# WheelDir_BoB.net
KiCad netlist of a schematic drawn in EAGLE
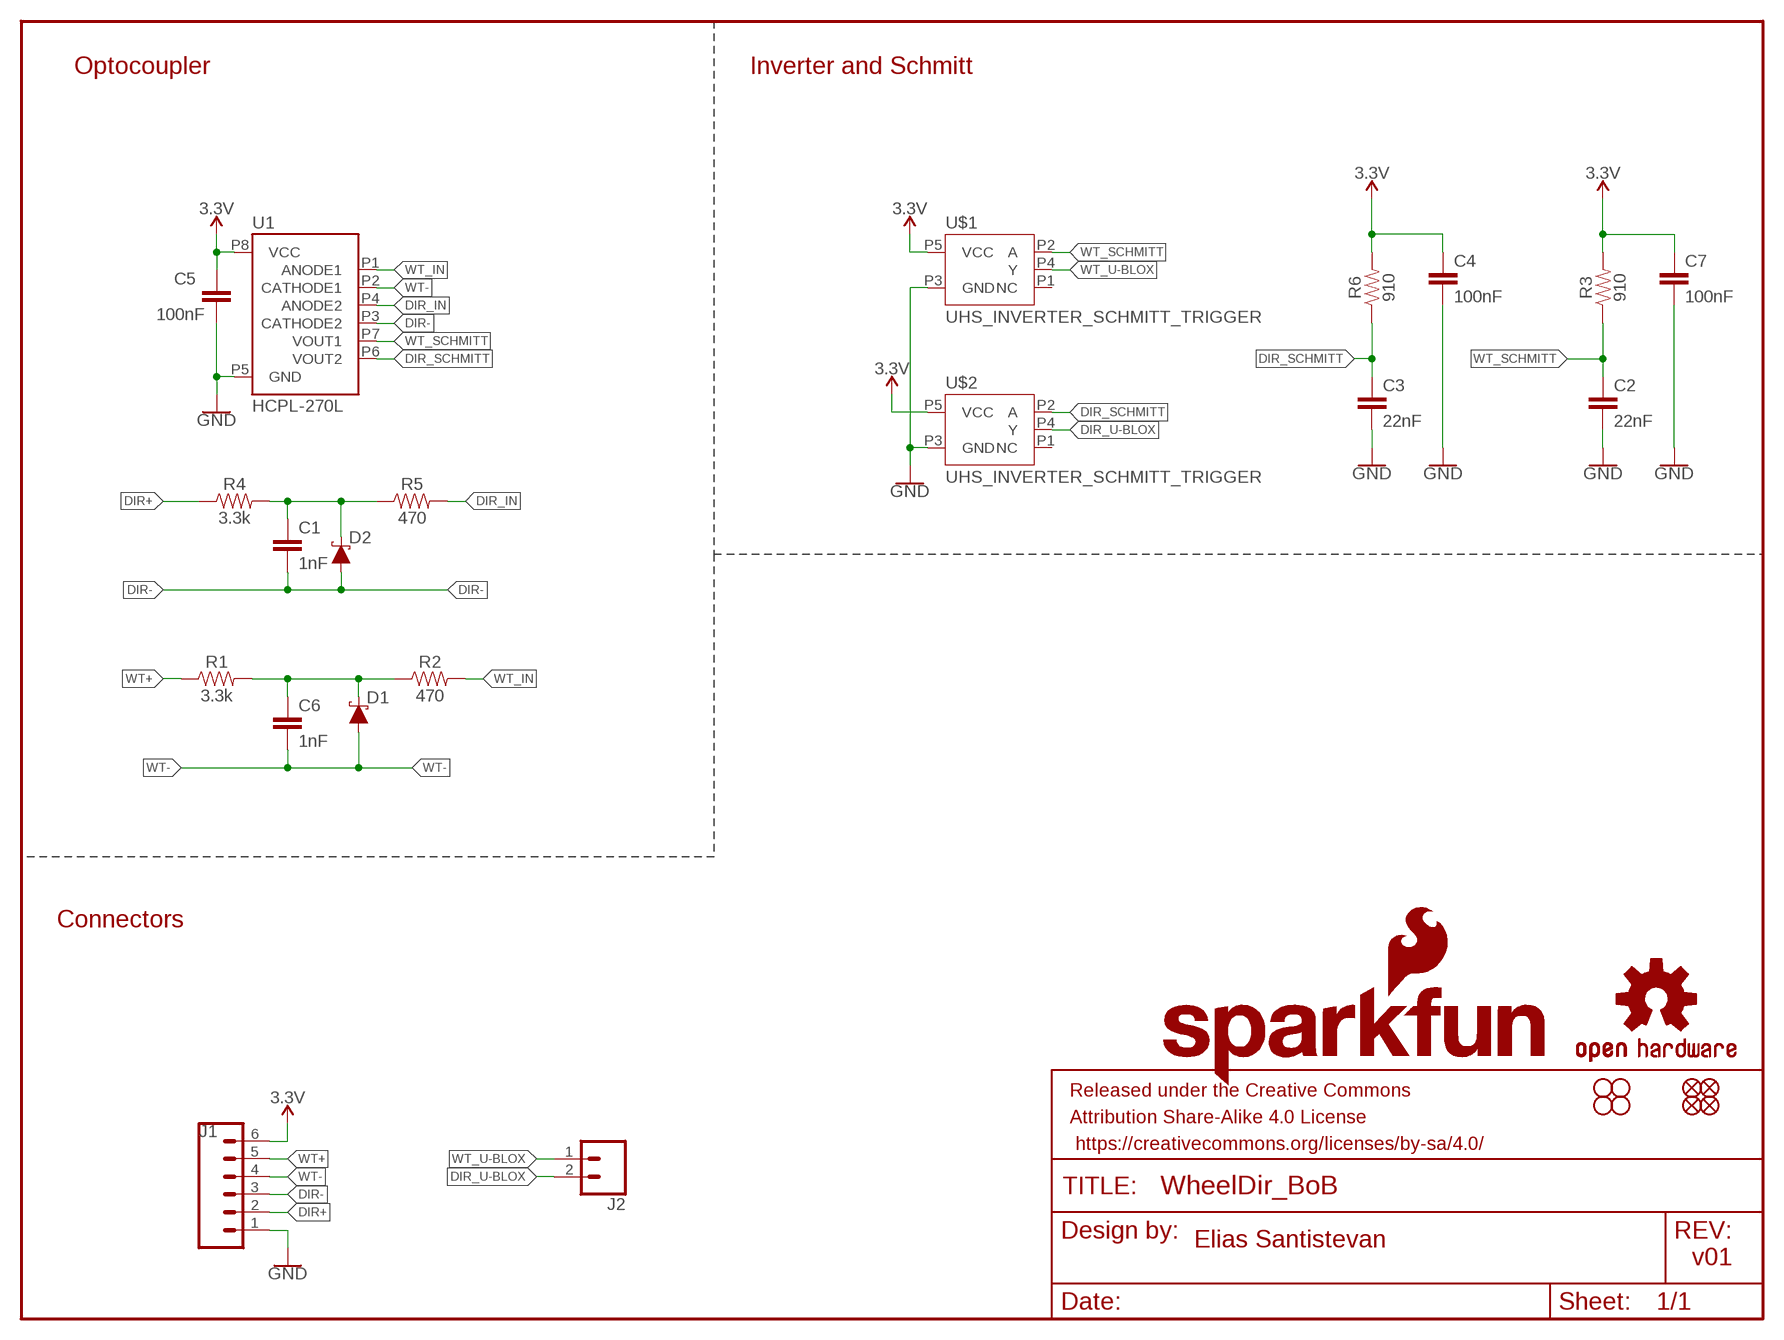
[diagram p0: schematic, sheet 1]

(export (version "E")
  (design (tool "Eeschema 10.0.6"))
  (components
    (comp (ref "C1")
      (value "1nF")
      (footprint "eagle-import:0603")
      (libsource (lib "eagle-import") (part "1.0NF/1000PF-0603-50V-10%"))
    )
    (comp (ref "C2")
      (value "22nF")
      (footprint "eagle-import:0603")
      (libsource (lib "eagle-import") (part "22NF/22,000PF-0603-50V-10%"))
    )
    (comp (ref "C3")
      (value "22nF")
      (footprint "eagle-import:0603")
      (libsource (lib "eagle-import") (part "22NF/22,000PF-0603-50V-10%"))
    )
    (comp (ref "C4")
      (value "100nF")
      (footprint "eagle-import:0603")
      (libsource (lib "eagle-import") (part "100NF-0603-10V-10%"))
    )
    (comp (ref "C5")
      (value "100nF")
      (footprint "eagle-import:0603")
      (libsource (lib "eagle-import") (part "100NF-0603-10V-10%"))
    )
    (comp (ref "C6")
      (value "1nF")
      (footprint "eagle-import:0603")
      (libsource (lib "eagle-import") (part "1.0NF/1000PF-0603-50V-10%"))
    )
    (comp (ref "C7")
      (value "100nF")
      (footprint "eagle-import:0603")
      (libsource (lib "eagle-import") (part "100NF-0603-10V-10%"))
    )
    (comp (ref "D1")
      (value "0.5A/40V/420mV")
      (footprint "eagle-import:SOD-323")
      (libsource (lib "eagle-import") (part "DIODE-SCHOTTKY-PMEG4005EJ"))
    )
    (comp (ref "D2")
      (value "0.5A/40V/420mV")
      (footprint "eagle-import:SOD-323")
      (libsource (lib "eagle-import") (part "DIODE-SCHOTTKY-PMEG4005EJ"))
    )
    (comp (ref "FD1")
      (value "FIDUCIALUFIDUCIAL")
      (footprint "eagle-import:FIDUCIAL-MICRO")
      (libsource (lib "eagle-import") (part "FIDUCIALUFIDUCIAL"))
    )
    (comp (ref "FD2")
      (value "FIDUCIALUFIDUCIAL")
      (footprint "eagle-import:FIDUCIAL-MICRO")
      (libsource (lib "eagle-import") (part "FIDUCIALUFIDUCIAL"))
    )
    (comp (ref "FD3")
      (value "FIDUCIALUFIDUCIAL")
      (footprint "eagle-import:FIDUCIAL-MICRO")
      (libsource (lib "eagle-import") (part "FIDUCIALUFIDUCIAL"))
    )
    (comp (ref "FD4")
      (value "FIDUCIALUFIDUCIAL")
      (footprint "eagle-import:FIDUCIAL-MICRO")
      (libsource (lib "eagle-import") (part "FIDUCIALUFIDUCIAL"))
    )
    (comp (ref "FRAME1")
      (value "FRAME-LETTER")
      (footprint "eagle-import:CREATIVE_COMMONS")
      (libsource (lib "eagle-import") (part "FRAME-LETTER"))
    )
    (comp (ref "H1")
      (value "STAND-OFF")
      (footprint "eagle-import:STAND-OFF")
      (libsource (lib "eagle-import") (part "STAND-OFF"))
    )
    (comp (ref "H2")
      (value "STAND-OFF")
      (footprint "eagle-import:STAND-OFF")
      (libsource (lib "eagle-import") (part "STAND-OFF"))
    )
    (comp (ref "H3")
      (value "STAND-OFF")
      (footprint "eagle-import:STAND-OFF")
      (libsource (lib "eagle-import") (part "STAND-OFF"))
    )
    (comp (ref "H4")
      (value "STAND-OFF")
      (footprint "eagle-import:STAND-OFF")
      (libsource (lib "eagle-import") (part "STAND-OFF"))
    )
    (comp (ref "J1")
      (value "CONN_06NO_SILK_NO_POP")
      (footprint "eagle-import:1X06_NO_SILK")
      (libsource (lib "eagle-import") (part "CONN_06NO_SILK_NO_POP"))
    )
    (comp (ref "J2")
      (value "CONN_021X02_NO_SILK")
      (footprint "eagle-import:1X02_NO_SILK")
      (libsource (lib "eagle-import") (part "CONN_021X02_NO_SILK"))
    )
    (comp (ref "LOGO1")
      (value "SFE_LOGO_NAME_FLAME.1_INCH")
      (footprint "eagle-import:SFE_LOGO_NAME_FLAME_.1")
      (libsource (lib "eagle-import") (part "SFE_LOGO_NAME_FLAME.1_INCH"))
    )
    (comp (ref "LOGO2")
      (value "OSHW-LOGOS")
      (footprint "eagle-import:OSHW-LOGO-S")
      (libsource (lib "eagle-import") (part "OSHW-LOGOS"))
    )
    (comp (ref "R1")
      (value "3.3k")
      (footprint "eagle-import:0603")
      (libsource (lib "eagle-import") (part "3.3KOHM-0603-1/10W-1%"))
    )
    (comp (ref "R2")
      (value "470")
      (footprint "eagle-import:0603")
      (libsource (lib "eagle-import") (part "470OHM-0603-1/10W-1%"))
    )
    (comp (ref "R3")
      (value "910")
      (footprint "eagle-import:0603")
      (libsource (lib "eagle-import") (part "910OHM-0603-1/10W-5%"))
    )
    (comp (ref "R4")
      (value "3.3k")
      (footprint "eagle-import:0603")
      (libsource (lib "eagle-import") (part "3.3KOHM-0603-1/10W-1%"))
    )
    (comp (ref "R5")
      (value "470")
      (footprint "eagle-import:0603")
      (libsource (lib "eagle-import") (part "470OHM-0603-1/10W-1%"))
    )
    (comp (ref "R6")
      (value "910")
      (footprint "eagle-import:0603")
      (libsource (lib "eagle-import") (part "910OHM-0603-1/10W-5%"))
    )
    (comp (ref "U$1")
      (value "UHS_INVERTER_SCHMITT_TRIGGER")
      (footprint "eagle-import:SC-74A")
      (libsource (lib "eagle-import") (part "UHS_INVERTER_SCHMITT_TRIGGER"))
    )
    (comp (ref "U$2")
      (value "UHS_INVERTER_SCHMITT_TRIGGER")
      (footprint "eagle-import:SC-74A")
      (libsource (lib "eagle-import") (part "UHS_INVERTER_SCHMITT_TRIGGER"))
    )
    (comp (ref "U1")
      (value "HCPL-270L")
      (footprint "eagle-import:SOP_8-PIN")
      (libsource (lib "eagle-import") (part "HCPL-270L"))
    )
  )
  (nets
    (net (code "1") (name "3.3V") (class "Default")
      (node (ref "C4") (pin "1") (pinfunction "1_1") (pintype "passive"))
      (node (ref "C5") (pin "1") (pinfunction "1_1") (pintype "passive"))
      (node (ref "C7") (pin "1") (pinfunction "1_1") (pintype "passive"))
      (node (ref "J1") (pin "6") (pinfunction "6_6") (pintype "passive"))
      (node (ref "R3") (pin "2") (pinfunction "2_2") (pintype "passive"))
      (node (ref "R6") (pin "2") (pinfunction "2_2") (pintype "passive"))
      (node (ref "U$1") (pin "P5") (pinfunction "VCC_P5") (pintype "power_in"))
      (node (ref "U$2") (pin "P5") (pinfunction "VCC_P5") (pintype "power_in"))
      (node (ref "U1") (pin "P8") (pinfunction "VCC_P8") (pintype "power_in"))
    )
    (net (code "2") (name "DIR+") (class "Default")
      (node (ref "J1") (pin "2") (pinfunction "2_2") (pintype "passive"))
      (node (ref "R4") (pin "1") (pinfunction "1_1") (pintype "passive"))
    )
    (net (code "3") (name "DIR-") (class "Default")
      (node (ref "C1") (pin "2") (pinfunction "2_2") (pintype "passive"))
      (node (ref "D2") (pin "A") (pinfunction "A_A") (pintype "passive"))
      (node (ref "J1") (pin "3") (pinfunction "3_3") (pintype "passive"))
      (node (ref "U1") (pin "P3") (pinfunction "CATHODE2_P3") (pintype "input"))
    )
    (net (code "4") (name "DIR_IN") (class "Default")
      (node (ref "R5") (pin "2") (pinfunction "2_2") (pintype "passive"))
      (node (ref "U1") (pin "P4") (pinfunction "ANODE2_P4") (pintype "input"))
    )
    (net (code "5") (name "DIR_SCHMITT") (class "Default")
      (node (ref "C3") (pin "1") (pinfunction "1_1") (pintype "passive"))
      (node (ref "R6") (pin "1") (pinfunction "1_1") (pintype "passive"))
      (node (ref "U$2") (pin "P2") (pinfunction "A_P2") (pintype "bidirectional"))
      (node (ref "U1") (pin "P6") (pinfunction "VOUT2_P6") (pintype "output"))
    )
    (net (code "6") (name "DIR_U-BLOX") (class "Default")
      (node (ref "J2") (pin "2") (pinfunction "2_2") (pintype "passive"))
      (node (ref "U$2") (pin "P4") (pinfunction "Y_P4") (pintype "bidirectional"))
    )
    (net (code "7") (name "GND") (class "Default")
      (node (ref "C2") (pin "2") (pinfunction "2_2") (pintype "passive"))
      (node (ref "C3") (pin "2") (pinfunction "2_2") (pintype "passive"))
      (node (ref "C4") (pin "2") (pinfunction "2_2") (pintype "passive"))
      (node (ref "C5") (pin "2") (pinfunction "2_2") (pintype "passive"))
      (node (ref "C7") (pin "2") (pinfunction "2_2") (pintype "passive"))
      (node (ref "J1") (pin "1") (pinfunction "1_1") (pintype "passive"))
      (node (ref "U$1") (pin "P3") (pinfunction "GND_P3") (pintype "power_in"))
      (node (ref "U$2") (pin "P3") (pinfunction "GND_P3") (pintype "power_in"))
      (node (ref "U1") (pin "P5") (pinfunction "GND_P5") (pintype "power_in"))
    )
    (net (code "8") (name "Net-(C1-Pad1)") (class "Default")
      (node (ref "C1") (pin "1") (pinfunction "1_1") (pintype "passive"))
      (node (ref "D2") (pin "C") (pinfunction "C_C") (pintype "passive"))
      (node (ref "R4") (pin "2") (pinfunction "2_2") (pintype "passive"))
      (node (ref "R5") (pin "1") (pinfunction "1_1") (pintype "passive"))
    )
    (net (code "9") (name "Net-(C6-Pad1)") (class "Default")
      (node (ref "C6") (pin "1") (pinfunction "1_1") (pintype "passive"))
      (node (ref "D1") (pin "C") (pinfunction "C_C") (pintype "passive"))
      (node (ref "R1") (pin "2") (pinfunction "2_2") (pintype "passive"))
      (node (ref "R2") (pin "1") (pinfunction "1_1") (pintype "passive"))
    )
    (net (code "10") (name "WT+") (class "Default")
      (node (ref "J1") (pin "5") (pinfunction "5_5") (pintype "passive"))
      (node (ref "R1") (pin "1") (pinfunction "1_1") (pintype "passive"))
    )
    (net (code "11") (name "WT-") (class "Default")
      (node (ref "C6") (pin "2") (pinfunction "2_2") (pintype "passive"))
      (node (ref "D1") (pin "A") (pinfunction "A_A") (pintype "passive"))
      (node (ref "J1") (pin "4") (pinfunction "4_4") (pintype "passive"))
      (node (ref "U1") (pin "P2") (pinfunction "CATHODE1_P2") (pintype "input"))
    )
    (net (code "12") (name "WT_IN") (class "Default")
      (node (ref "R2") (pin "2") (pinfunction "2_2") (pintype "passive"))
      (node (ref "U1") (pin "P1") (pinfunction "ANODE1_P1") (pintype "input"))
    )
    (net (code "13") (name "WT_SCHMITT") (class "Default")
      (node (ref "C2") (pin "1") (pinfunction "1_1") (pintype "passive"))
      (node (ref "R3") (pin "1") (pinfunction "1_1") (pintype "passive"))
      (node (ref "U$1") (pin "P2") (pinfunction "A_P2") (pintype "bidirectional"))
      (node (ref "U1") (pin "P7") (pinfunction "VOUT1_P7") (pintype "output"))
    )
    (net (code "14") (name "WT_U-BLOX") (class "Default")
      (node (ref "J2") (pin "1") (pinfunction "1_1") (pintype "passive"))
      (node (ref "U$1") (pin "P4") (pinfunction "Y_P4") (pintype "bidirectional"))
    )
    (net (code "15") (name "unconnected-(U$1-NC-PadP1)") (class "Default")
      (node (ref "U$1") (pin "P1") (pinfunction "NC_P1") (pintype "no_connect"))
    )
    (net (code "16") (name "unconnected-(U$2-NC-PadP1)") (class "Default")
      (node (ref "U$2") (pin "P1") (pinfunction "NC_P1") (pintype "no_connect"))
    )
  )
)
